# BPMicrocontroller.net
KiCad netlist of a schematic drawn in Altium Designer
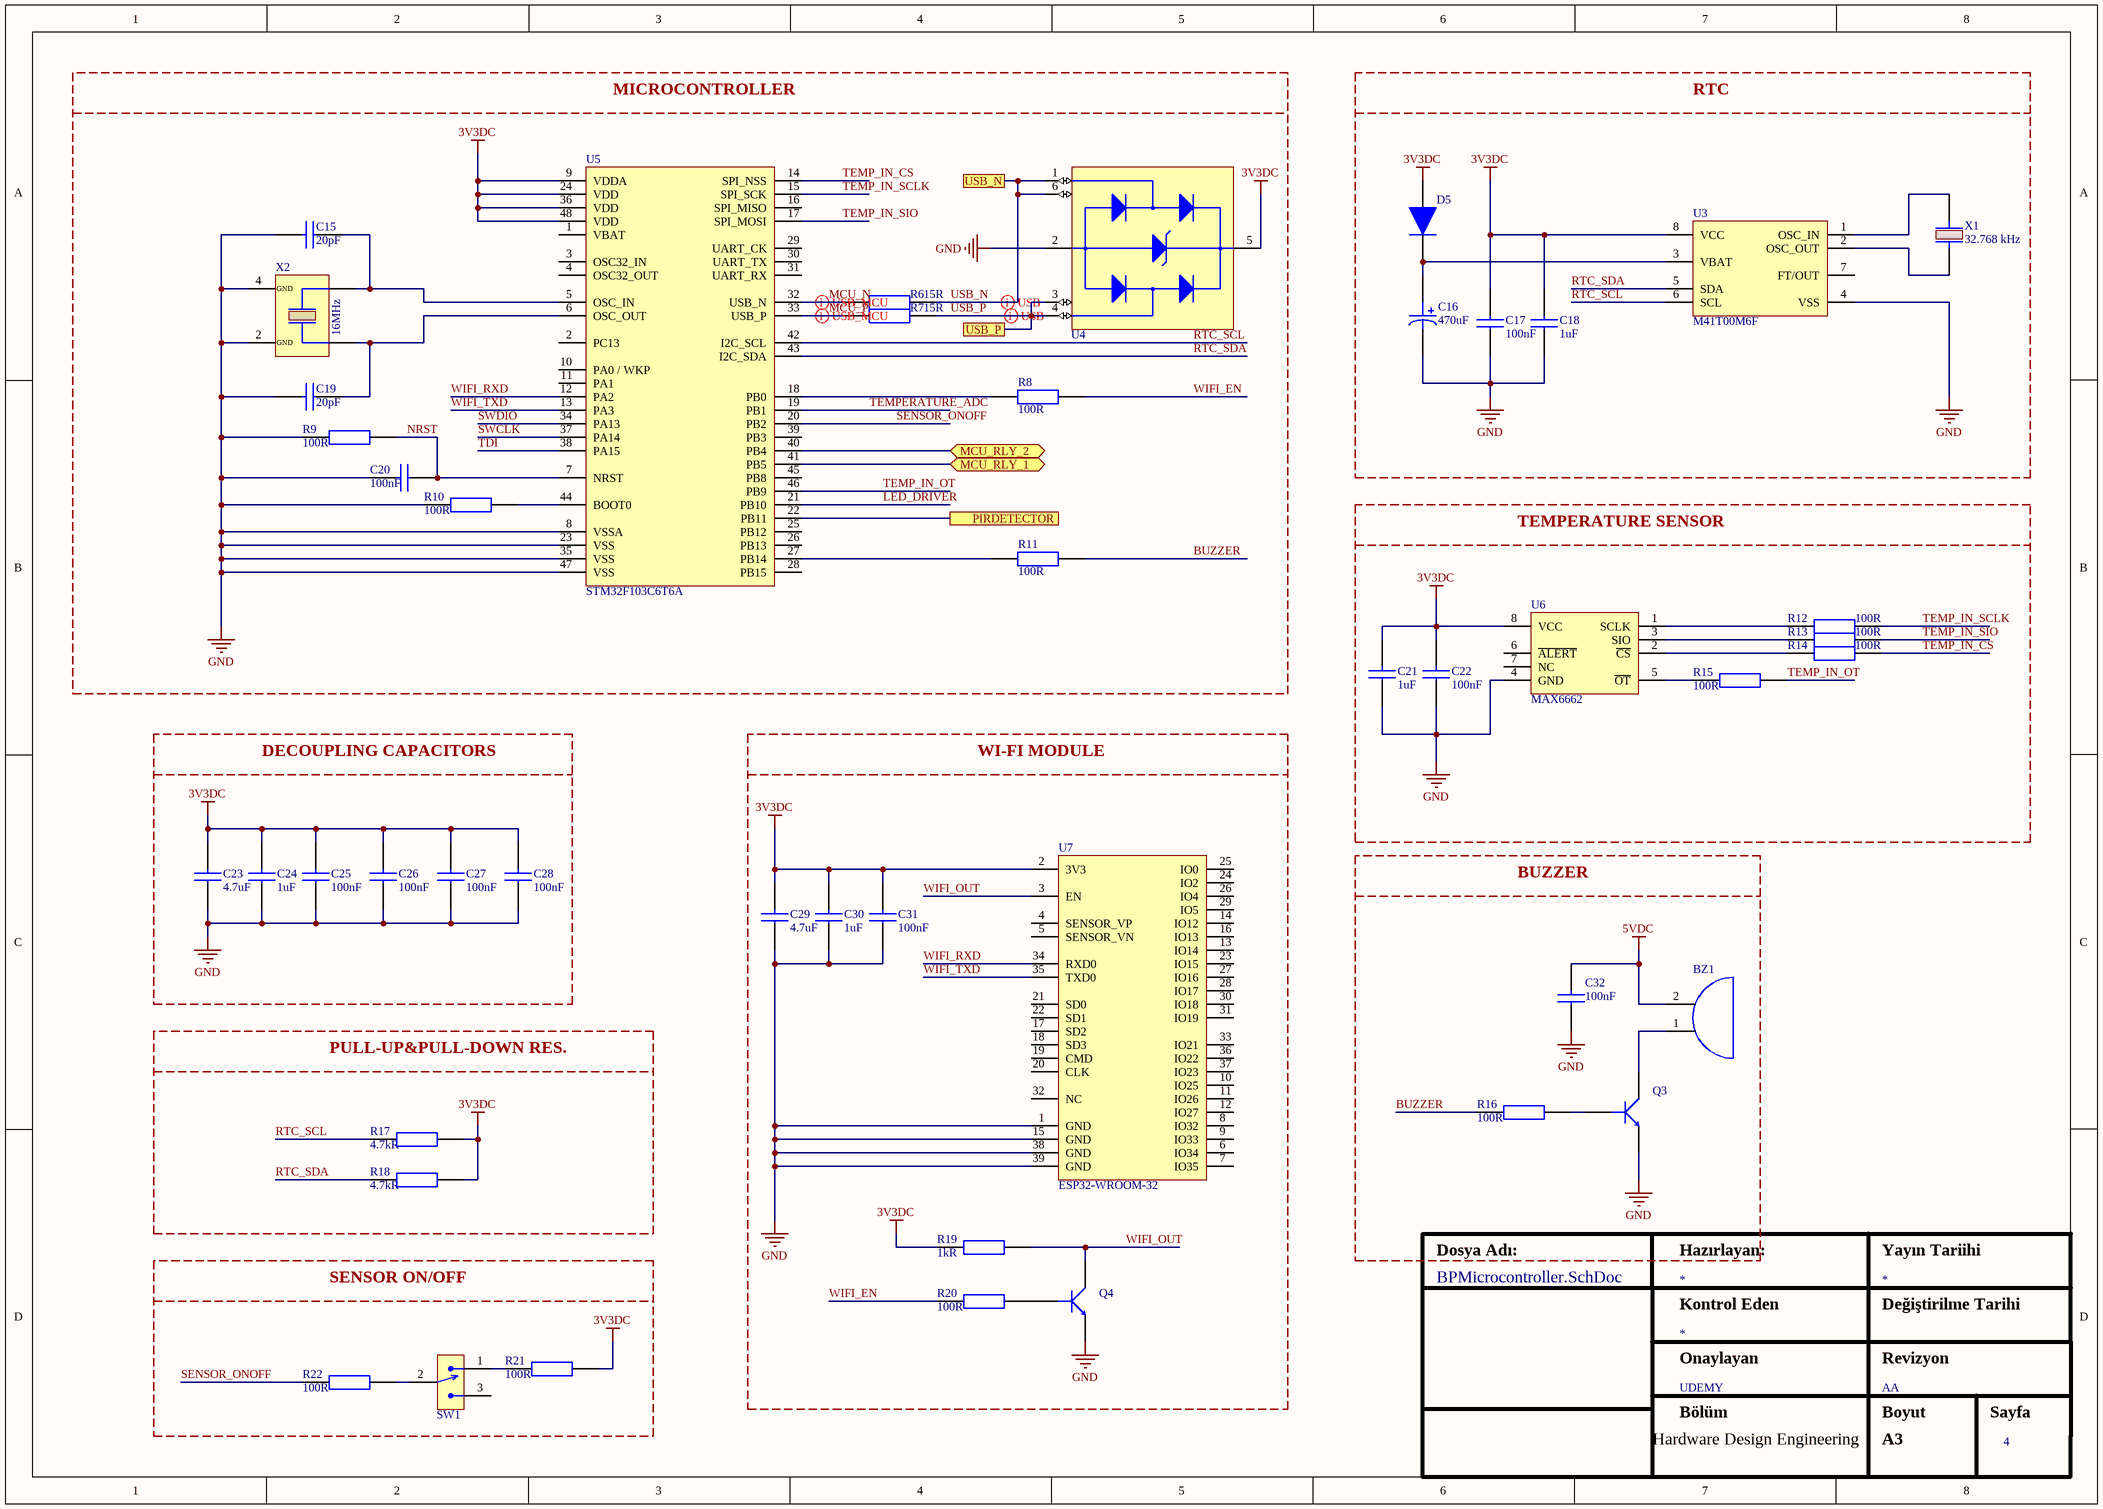
[diagram p0: BPMicrocontroller.SchDoc]

(export (version "E")
  (design (tool "Eeschema 10.0.6"))
  (components
    (comp (ref "BZ1")
      (value "CMI-9605IC-0580T")
      (footprint "CMI-9605IC")
      (description "Buzzers Indicator, Internally Driven Magnetic 5V 30mA 2.7kHz 80dB @ 5V, 10cm Through Hole PC Pins")
      (fields (field (name "MANUFACTURER") "CUI Devices") (field (name "DESIGNED BY") "BERK"))
      (libsource (lib "UDEMY_Library") (part "CMI-9605IC-0580T"))
    )
    (comp (ref "C15")
      (value "CL10C200JB8NNNC")
      (footprint "CAP_0603")
      (description "CAP CER 20pF %5 0603 SMD")
      (fields
        (field (name "MANUFACTURER") "Samsung")
        (field (name "TOLERANCE") "5%")
        (field (name "CAPACITANCE") "20pF")
        (field (name "DESIGNED BY") "BERK")
      )
      (libsource (lib "UDEMY_Library") (part "CAP CER 20pF 0603"))
    )
    (comp (ref "C16")
      (value "ESH477M050AH4AA")
      (footprint "CAP_RADIAL_D10_P5")
      (description "CAP ALU ELEC 470uF 50V RADIAL")
      (fields
        (field (name "MANUFACTURER") "KEMET")
        (field (name "TOLERANCE") "20%")
        (field (name "CAPACITANCE") "470uF")
        (field (name "DESIGNED BY") "BERK")
      )
      (libsource (lib "UDEMY_Library") (part "CAP ALU ELEC 470uF 50V"))
    )
    (comp (ref "C17")
      (value "CL21B104KBCNNNC")
      (footprint "CAP_0805")
      (description "CAP CER 100nF %10 0805")
      (fields
        (field (name "MANUFACTURER") "Samsung")
        (field (name "TOLERANCE") "10%")
        (field (name "CAPACITANCE") "100nF")
        (field (name "DESIGNED BY") "BERK")
      )
      (libsource (lib "UDEMY_Library") (part "CAP CER 100nF 0805"))
    )
    (comp (ref "C18")
      (value "CL21B105KBFNNNE")
      (footprint "CAP_0805")
      (description "CAP CER 1uF %10 0805")
      (fields
        (field (name "MANUFACTURER") "Samsung")
        (field (name "TOLERANCE") "10%")
        (field (name "CAPACITANCE") "1uF")
        (field (name "DESIGNED BY") "BERK")
      )
      (libsource (lib "UDEMY_Library") (part "CAP CER 1uF 0805"))
    )
    (comp (ref "C19")
      (value "CL10C200JB8NNNC")
      (footprint "CAP_0603")
      (description "CAP CER 20pF %5 0603 SMD")
      (fields
        (field (name "MANUFACTURER") "Samsung")
        (field (name "TOLERANCE") "5%")
        (field (name "CAPACITANCE") "20pF")
        (field (name "DESIGNED BY") "BERK")
      )
      (libsource (lib "UDEMY_Library") (part "CAP CER 20pF 0603"))
    )
    (comp (ref "C20")
      (value "C0603C104K5RACTU")
      (footprint "CAP_0603")
      (description "CAP CER 100nF %10 0603 SMD")
      (fields
        (field (name "MANUFACTURER") "KEMET")
        (field (name "TOLERANCE") "10%")
        (field (name "CAPACITANCE") "100nF")
        (field (name "DESIGNED BY") "BERK")
      )
      (libsource (lib "UDEMY_Library") (part "CAP CER 100nF 0603"))
    )
    (comp (ref "C21")
      (value "CL21B105KBFNNNE")
      (footprint "CAP_0805")
      (description "CAP CER 1uF %10 0805")
      (fields
        (field (name "MANUFACTURER") "Samsung")
        (field (name "TOLERANCE") "10%")
        (field (name "CAPACITANCE") "1uF")
        (field (name "DESIGNED BY") "BERK")
      )
      (libsource (lib "UDEMY_Library") (part "CAP CER 1uF 0805"))
    )
    (comp (ref "C22")
      (value "CL21B104KBCNNNC")
      (footprint "CAP_0805")
      (description "CAP CER 100nF %10 0805")
      (fields
        (field (name "MANUFACTURER") "Samsung")
        (field (name "TOLERANCE") "10%")
        (field (name "CAPACITANCE") "100nF")
        (field (name "DESIGNED BY") "BERK")
      )
      (libsource (lib "UDEMY_Library") (part "CAP CER 100nF 0805"))
    )
    (comp (ref "C23")
      (value "CL21A475KAQNNNE")
      (footprint "CAP_0805")
      (description "CAP CER 4.7uF %10 0805")
      (fields
        (field (name "MANUFACTURER") "Samsung")
        (field (name "TOLERANCE") "10%")
        (field (name "CAPACITANCE") "4.7uF")
        (field (name "DESIGNED BY") "BERK")
      )
      (libsource (lib "UDEMY_Library") (part "CAP CER 4.7uF 0805"))
    )
    (comp (ref "C24")
      (value "CL21B105KBFNNNE")
      (footprint "CAP_0805")
      (description "CAP CER 1uF %10 0805")
      (fields
        (field (name "MANUFACTURER") "Samsung")
        (field (name "TOLERANCE") "10%")
        (field (name "CAPACITANCE") "1uF")
        (field (name "DESIGNED BY") "BERK")
      )
      (libsource (lib "UDEMY_Library") (part "CAP CER 1uF 0805"))
    )
    (comp (ref "C25")
      (value "C0603C104K5RACTU")
      (footprint "CAP_0603")
      (description "CAP CER 100nF %10 0603 SMD")
      (fields
        (field (name "MANUFACTURER") "KEMET")
        (field (name "TOLERANCE") "10%")
        (field (name "CAPACITANCE") "100nF")
        (field (name "DESIGNED BY") "BERK")
      )
      (libsource (lib "UDEMY_Library") (part "CAP CER 100nF 0603"))
    )
    (comp (ref "C26")
      (value "C0603C104K5RACTU")
      (footprint "CAP_0603")
      (description "CAP CER 100nF %10 0603 SMD")
      (fields
        (field (name "MANUFACTURER") "KEMET")
        (field (name "TOLERANCE") "10%")
        (field (name "CAPACITANCE") "100nF")
        (field (name "DESIGNED BY") "BERK")
      )
      (libsource (lib "UDEMY_Library") (part "CAP CER 100nF 0603"))
    )
    (comp (ref "C27")
      (value "C0603C104K5RACTU")
      (footprint "CAP_0603")
      (description "CAP CER 100nF %10 0603 SMD")
      (fields
        (field (name "MANUFACTURER") "KEMET")
        (field (name "TOLERANCE") "10%")
        (field (name "CAPACITANCE") "100nF")
        (field (name "DESIGNED BY") "BERK")
      )
      (libsource (lib "UDEMY_Library") (part "CAP CER 100nF 0603"))
    )
    (comp (ref "C28")
      (value "C0603C104K5RACTU")
      (footprint "CAP_0603")
      (description "CAP CER 100nF %10 0603 SMD")
      (fields
        (field (name "MANUFACTURER") "KEMET")
        (field (name "TOLERANCE") "10%")
        (field (name "CAPACITANCE") "100nF")
        (field (name "DESIGNED BY") "BERK")
      )
      (libsource (lib "UDEMY_Library") (part "CAP CER 100nF 0603"))
    )
    (comp (ref "C29")
      (value "CL21A475KAQNNNE")
      (footprint "CAP_0805")
      (description "CAP CER 4.7uF %10 0805")
      (fields
        (field (name "MANUFACTURER") "Samsung")
        (field (name "TOLERANCE") "10%")
        (field (name "CAPACITANCE") "4.7uF")
        (field (name "DESIGNED BY") "BERK")
      )
      (libsource (lib "UDEMY_Library") (part "CAP CER 4.7uF 0805"))
    )
    (comp (ref "C30")
      (value "CL21B105KBFNNNE")
      (footprint "CAP_0805")
      (description "CAP CER 1uF %10 0805")
      (fields
        (field (name "MANUFACTURER") "Samsung")
        (field (name "TOLERANCE") "10%")
        (field (name "CAPACITANCE") "1uF")
        (field (name "DESIGNED BY") "BERK")
      )
      (libsource (lib "UDEMY_Library") (part "CAP CER 1uF 0805"))
    )
    (comp (ref "C31")
      (value "CL21B104KBCNNNC")
      (footprint "CAP_0805")
      (description "CAP CER 100nF %10 0805")
      (fields
        (field (name "MANUFACTURER") "Samsung")
        (field (name "TOLERANCE") "10%")
        (field (name "CAPACITANCE") "100nF")
        (field (name "DESIGNED BY") "BERK")
      )
      (libsource (lib "UDEMY_Library") (part "CAP CER 100nF 0805"))
    )
    (comp (ref "C32")
      (value "CL21B104KBCNNNC")
      (footprint "CAP_0805")
      (description "CAP CER 100nF %10 0805")
      (fields
        (field (name "MANUFACTURER") "Samsung")
        (field (name "TOLERANCE") "10%")
        (field (name "CAPACITANCE") "100nF")
        (field (name "DESIGNED BY") "BERK")
      )
      (libsource (lib "UDEMY_Library") (part "CAP CER 100nF 0805"))
    )
    (comp (ref "D5")
      (value "1N4148WS")
      (footprint "SOD323F")
      (description "Diode, Single, 75 V, 150 mA, 1 V, 4 ns")
      (fields
        (field (name "MANUFACTURER") "ON Semiconductor / Fairchild")
        (field (name "DESIGNED BY") "BERK")
      )
      (libsource (lib "UDEMY_Library") (part "1N4148WS"))
    )
    (comp (ref "Q3")
      (value "MMBT3904-7-F")
      (footprint "SOT-23F")
      (description "Transistor General Purpose BJT NPN 40 Volt 0.2A Automotive 3-Pin SOT-23")
      (fields (field (name "MANUFACTURER") "Diodes Zetex") (field (name "DESIGNED BY") "BERK"))
      (libsource (lib "UDEMY_Library") (part "MMBT3904-7-F"))
    )
    (comp (ref "Q4")
      (value "MMBT3904-7-F")
      (footprint "SOT-23F")
      (description "Transistor General Purpose BJT NPN 40 Volt 0.2A Automotive 3-Pin SOT-23")
      (fields (field (name "MANUFACTURER") "Diodes Zetex") (field (name "DESIGNED BY") "BERK"))
      (libsource (lib "UDEMY_Library") (part "MMBT3904-7-F"))
    )
    (comp (ref "R6")
      (value "RC0603JR-0715RL")
      (footprint "RES_0603")
      (description "RES 15 %5 OHM 0603 SMD")
      (fields
        (field (name "MANUFACTURER") "Yageo")
        (field (name "TOLERANCE") "5%")
        (field (name "RESISTANCE") "15R")
        (field (name "DESIGNED BY") "BERK")
      )
      (libsource (lib "UDEMY_Library") (part "RES 15 OHM 0603"))
    )
    (comp (ref "R7")
      (value "RC0603JR-0715RL")
      (footprint "RES_0603")
      (description "RES 15 %5 OHM 0603 SMD")
      (fields
        (field (name "MANUFACTURER") "Yageo")
        (field (name "TOLERANCE") "5%")
        (field (name "RESISTANCE") "15R")
        (field (name "DESIGNED BY") "BERK")
      )
      (libsource (lib "UDEMY_Library") (part "RES 15 OHM 0603"))
    )
    (comp (ref "R8")
      (value "RC0603JR-07100RL")
      (footprint "RES_0603")
      (description "RES 100 %5 OHM 0603 SMD")
      (fields
        (field (name "MANUFACTURER") "Yageo")
        (field (name "TOLERANCE") "5%")
        (field (name "RESISTANCE") "100R")
        (field (name "DESIGNED BY") "BERK")
      )
      (libsource (lib "UDEMY_Library") (part "RES 100 OHM 0603"))
    )
    (comp (ref "R9")
      (value "RC0603JR-07100RL")
      (footprint "RES_0603")
      (description "RES 100 %5 OHM 0603 SMD")
      (fields
        (field (name "MANUFACTURER") "Yageo")
        (field (name "TOLERANCE") "5%")
        (field (name "RESISTANCE") "100R")
        (field (name "DESIGNED BY") "BERK")
      )
      (libsource (lib "UDEMY_Library") (part "RES 100 OHM 0603"))
    )
    (comp (ref "R10")
      (value "RC0603JR-07100RL")
      (footprint "RES_0603")
      (description "RES 100 %5 OHM 0603 SMD")
      (fields
        (field (name "MANUFACTURER") "Yageo")
        (field (name "TOLERANCE") "5%")
        (field (name "RESISTANCE") "100R")
        (field (name "DESIGNED BY") "BERK")
      )
      (libsource (lib "UDEMY_Library") (part "RES 100 OHM 0603"))
    )
    (comp (ref "R11")
      (value "RC0603JR-07100RL")
      (footprint "RES_0603")
      (description "RES 100 %5 OHM 0603 SMD")
      (fields
        (field (name "MANUFACTURER") "Yageo")
        (field (name "TOLERANCE") "5%")
        (field (name "RESISTANCE") "100R")
        (field (name "DESIGNED BY") "BERK")
      )
      (libsource (lib "UDEMY_Library") (part "RES 100 OHM 0603"))
    )
    (comp (ref "R12")
      (value "RC0603JR-07100RL")
      (footprint "RES_0603")
      (description "RES 100 %5 OHM 0603 SMD")
      (fields
        (field (name "MANUFACTURER") "Yageo")
        (field (name "TOLERANCE") "5%")
        (field (name "RESISTANCE") "100R")
        (field (name "DESIGNED BY") "BERK")
      )
      (libsource (lib "UDEMY_Library") (part "RES 100 OHM 0603"))
    )
    (comp (ref "R13")
      (value "RC0603JR-07100RL")
      (footprint "RES_0603")
      (description "RES 100 %5 OHM 0603 SMD")
      (fields
        (field (name "MANUFACTURER") "Yageo")
        (field (name "TOLERANCE") "5%")
        (field (name "RESISTANCE") "100R")
        (field (name "DESIGNED BY") "BERK")
      )
      (libsource (lib "UDEMY_Library") (part "RES 100 OHM 0603"))
    )
    (comp (ref "R14")
      (value "RC0603JR-07100RL")
      (footprint "RES_0603")
      (description "RES 100 %5 OHM 0603 SMD")
      (fields
        (field (name "MANUFACTURER") "Yageo")
        (field (name "TOLERANCE") "5%")
        (field (name "RESISTANCE") "100R")
        (field (name "DESIGNED BY") "BERK")
      )
      (libsource (lib "UDEMY_Library") (part "RES 100 OHM 0603"))
    )
    (comp (ref "R15")
      (value "RC0603JR-07100RL")
      (footprint "RES_0603")
      (description "RES 100 %5 OHM 0603 SMD")
      (fields
        (field (name "MANUFACTURER") "Yageo")
        (field (name "TOLERANCE") "5%")
        (field (name "RESISTANCE") "100R")
        (field (name "DESIGNED BY") "BERK")
      )
      (libsource (lib "UDEMY_Library") (part "RES 100 OHM 0603"))
    )
    (comp (ref "R16")
      (value "RC0603JR-07100RL")
      (footprint "RES_0603")
      (description "RES 100 %5 OHM 0603 SMD")
      (fields
        (field (name "MANUFACTURER") "Yageo")
        (field (name "TOLERANCE") "5%")
        (field (name "RESISTANCE") "100R")
        (field (name "DESIGNED BY") "BERK")
      )
      (libsource (lib "UDEMY_Library") (part "RES 100 OHM 0603"))
    )
    (comp (ref "R17")
      (value "RC0603JR-074K7L")
      (footprint "RES_0603")
      (description "RES 4K7 %5 OHM 0603 SMD")
      (fields
        (field (name "MANUFACTURER") "Yageo")
        (field (name "TOLERANCE") "5%")
        (field (name "RESISTANCE") "4.7kR")
        (field (name "DESIGNED BY") "BERK")
      )
      (libsource (lib "UDEMY_Library") (part "RES 4K7 OHM 0603"))
    )
    (comp (ref "R18")
      (value "RC0603JR-074K7L")
      (footprint "RES_0603")
      (description "RES 4K7 %5 OHM 0603 SMD")
      (fields
        (field (name "MANUFACTURER") "Yageo")
        (field (name "TOLERANCE") "5%")
        (field (name "RESISTANCE") "4.7kR")
        (field (name "DESIGNED BY") "BERK")
      )
      (libsource (lib "UDEMY_Library") (part "RES 4K7 OHM 0603"))
    )
    (comp (ref "R19")
      (value "RC0603FR-0710KL")
      (footprint "RES_0603")
      (description "RES 1K %1 OHM 0603 SMD")
      (fields
        (field (name "MANUFACTURER") "Yageo")
        (field (name "MANUFACTURER PART NUMBER") "RC0603JR-071KL")
        (field (name "RESISTANCE") "1kR")
        (field (name "DESIGNED BY") "BERK")
      )
      (libsource (lib "UDEMY_Library") (part "RES 1K OHM 0603"))
    )
    (comp (ref "R20")
      (value "RC0603JR-07100RL")
      (footprint "RES_0603")
      (description "RES 100 %5 OHM 0603 SMD")
      (fields
        (field (name "MANUFACTURER") "Yageo")
        (field (name "TOLERANCE") "5%")
        (field (name "RESISTANCE") "100R")
        (field (name "DESIGNED BY") "BERK")
      )
      (libsource (lib "UDEMY_Library") (part "RES 100 OHM 0603"))
    )
    (comp (ref "R21")
      (value "RC0603JR-07100RL")
      (footprint "RES_0603")
      (description "RES 100 %5 OHM 0603 SMD")
      (fields
        (field (name "MANUFACTURER") "Yageo")
        (field (name "TOLERANCE") "5%")
        (field (name "RESISTANCE") "100R")
        (field (name "DESIGNED BY") "BERK")
      )
      (libsource (lib "UDEMY_Library") (part "RES 100 OHM 0603"))
    )
    (comp (ref "R22")
      (value "RC0603JR-07100RL")
      (footprint "RES_0603")
      (description "RES 100 %5 OHM 0603 SMD")
      (fields
        (field (name "MANUFACTURER") "Yageo")
        (field (name "TOLERANCE") "5%")
        (field (name "RESISTANCE") "100R")
        (field (name "DESIGNED BY") "BERK")
      )
      (libsource (lib "") (part "RES 100 OHM 0603_1"))
    )
    (comp (ref "SW1")
      (value "EG1215AA")
      (footprint "EG1215AA")
      (description "Slide Switch, SPDT, 0.025A, 24V, SMD")
      (fields
        (field (name "MANUFACTURER") "E-Switch")
        (field (name "TOLERANCE") "4.95%")
        (field (name "DESIGNED BY") "BERK")
      )
      (libsource (lib "UDEMY_Library") (part "EG1215AA"))
    )
    (comp (ref "U3")
      (value "M41T00M6F")
      (footprint "SOIC8")
      (description "IC RTC CLK/CALENDAR I2C 8-SOIC")
      (fields (field (name "MANUFACTURER") "STMicroelectronics") (field (name "DESIGNED BY") "BERK"))
      (libsource (lib "UDEMY_Library") (part "M41T00M6F"))
    )
    (comp (ref "U4")
      (value "USBLC6-2SC6")
      (footprint "SOT23-6L")
      (description "TVS DIODE 5.25V 17V SOT23-6")
      (fields (field (name "MANUFACTURER") "STMicroelectronics") (field (name "DESIGNED BY") "BERK"))
      (libsource (lib "UDEMY_Library") (part "USB PROTECTION"))
    )
    (comp (ref "U5")
      (value "STM32F103C6T6A")
      (footprint "LQFP-48")
      (description "MCU 32-bit STM32F ARM Cortex M3 RISC 32KB Flash 2.5V/3.3V 48-Pin LQFP Tray")
      (fields (field (name "MANUFACTURER") "STMicroelectronics") (field (name "DESIGNED BY") "BERK"))
      (libsource (lib "UDEMY_Library") (part "STM32F103C6T6A"))
    )
    (comp (ref "U6")
      (value "MAX6662")
      (footprint "SOIC8")
      (description "SENSOR TEMPERATURE SPI 8SOIC")
      (fields
        (field (name "MANUFACTURER") "Maxim")
        (field (name "MANUFACTURER PART NUMBER") "MAX6662MSA+")
        (field (name "DESIGNED BY") "BERK")
      )
      (libsource (lib "UDEMY_Library") (part "MAX6662"))
    )
    (comp (ref "U7")
      (value "ESP32-WROOM-32")
      (footprint "ESP32-32")
      (description "SMD MODULE, ESP32-D0WDQ6, 32MBIT")
      (fields (field (name "MANUFACTURER") "Espressif Systems") (field (name "DESIGNED BY") "BERK"))
      (libsource (lib "UDEMY_Library") (part "ESP32-WROOM-32"))
    )
    (comp (ref "X1")
      (value "ABS05-32.768KHZ-T")
      (footprint "BPSchematic:ABS05")
      (description "Crystal, 32.768 kHz, SMD, 1.6mm x 1mm, 12.5 pF, 20 ppm, ABS05 Series")
      (fields
        (field (name "MANUFACTURER") "Abracon")
        (field (name "TOLERANCE") "20ppm")
        (field (name "OPERATING FREQUENCY") "32.768 kHz")
        (field (name "DESIGNED BY") "BERK")
      )
      (libsource (lib "UDEMY_Library") (part "CRYSTAL 32768kHZ"))
    )
    (comp (ref "X2")
      (value "ECS-160-20-30B-TR")
      (footprint "ECS")
      (description "CRYSTAL 16.0000MHZ 20PF SMD")
      (fields
        (field (name "MANUFACTURER") "ECS International")
        (field (name "TOLERANCE") "50ppm")
        (field (name "FREQUENCY") "16MHz")
        (field (name "DESIGNED BY") "BERK")
      )
      (libsource (lib "UDEMY_Library") (part "CRYSTAL 16MHz"))
    )
  )
  (nets
    (net (code "1") (name "/BUZZER") (class "Default")
      (node (ref "R11") (pin "2") (pinfunction "2_2") (pintype "passive"))
      (node (ref "R16") (pin "1") (pinfunction "1_1") (pintype "passive"))
    )
    (net (code "2") (name "/LED_DRIVER") (class "Default")
      (node (ref "U5") (pin "21") (pinfunction "PB10_21") (pintype "passive"))
    )
    (net (code "3") (name "/MCU_N") (class "Default")
      (node (ref "R6") (pin "1") (pinfunction "1_1") (pintype "passive"))
      (node (ref "U5") (pin "32") (pinfunction "USB_N_32") (pintype "passive"))
    )
    (net (code "4") (name "/MCU_P") (class "Default")
      (node (ref "R7") (pin "1") (pinfunction "1_1") (pintype "passive"))
      (node (ref "U5") (pin "33") (pinfunction "USB_P_33") (pintype "passive"))
    )
    (net (code "5") (name "/MCU_RLY_1") (class "Default")
      (node (ref "U5") (pin "41") (pinfunction "PB5_41") (pintype "passive"))
    )
    (net (code "6") (name "/MCU_RLY_2") (class "Default")
      (node (ref "U5") (pin "40") (pinfunction "PB4_40") (pintype "passive"))
    )
    (net (code "7") (name "/NRST") (class "Default")
      (node (ref "C20") (pin "1") (pinfunction "1_1") (pintype "passive"))
      (node (ref "R9") (pin "2") (pinfunction "2_2") (pintype "passive"))
      (node (ref "U5") (pin "7") (pinfunction "NRST_7") (pintype "passive"))
    )
    (net (code "8") (name "/PIRDETECTOR") (class "Default")
      (node (ref "U5") (pin "22") (pinfunction "PB11_22") (pintype "passive"))
    )
    (net (code "9") (name "/RTC_SCL") (class "Default")
      (node (ref "R17") (pin "1") (pinfunction "1_1") (pintype "passive"))
      (node (ref "U3") (pin "6") (pinfunction "SCL_6") (pintype "passive"))
      (node (ref "U5") (pin "42") (pinfunction "I2C_SCL_42") (pintype "passive"))
    )
    (net (code "10") (name "/RTC_SDA") (class "Default")
      (node (ref "R18") (pin "1") (pinfunction "1_1") (pintype "passive"))
      (node (ref "U3") (pin "5") (pinfunction "SDA_5") (pintype "passive"))
      (node (ref "U5") (pin "43") (pinfunction "I2C_SDA_43") (pintype "passive"))
    )
    (net (code "11") (name "/SENSOR_ONOFF") (class "Default")
      (node (ref "R22") (pin "2") (pinfunction "2_2") (pintype "passive"))
      (node (ref "U5") (pin "20") (pinfunction "PB2_20") (pintype "passive"))
    )
    (net (code "12") (name "/SWCLK") (class "Default")
      (node (ref "U5") (pin "37") (pinfunction "PA14_37") (pintype "passive"))
    )
    (net (code "13") (name "/SWDIO") (class "Default")
      (node (ref "U5") (pin "34") (pinfunction "PA13_34") (pintype "passive"))
    )
    (net (code "14") (name "/TDI") (class "Default")
      (node (ref "U5") (pin "38") (pinfunction "PA15_38") (pintype "passive"))
    )
    (net (code "15") (name "/TEMPERATURE_ADC") (class "Default")
      (node (ref "U5") (pin "19") (pinfunction "PB1_19") (pintype "passive"))
    )
    (net (code "16") (name "/TEMP_IN_CS") (class "Default")
      (node (ref "R14") (pin "2") (pinfunction "2_2") (pintype "passive"))
      (node (ref "U5") (pin "14") (pinfunction "SPI_NSS_14") (pintype "passive"))
    )
    (net (code "17") (name "/TEMP_IN_OT") (class "Default")
      (node (ref "R15") (pin "2") (pinfunction "2_2") (pintype "passive"))
      (node (ref "U5") (pin "46") (pinfunction "PB9_46") (pintype "passive"))
    )
    (net (code "18") (name "/TEMP_IN_SCLK") (class "Default")
      (node (ref "R12") (pin "2") (pinfunction "2_2") (pintype "passive"))
      (node (ref "U5") (pin "15") (pinfunction "SPI_SCK_15") (pintype "passive"))
    )
    (net (code "19") (name "/TEMP_IN_SIO") (class "Default")
      (node (ref "R13") (pin "2") (pinfunction "2_2") (pintype "passive"))
      (node (ref "U5") (pin "17") (pinfunction "SPI_MOSI_17") (pintype "passive"))
    )
    (net (code "20") (name "/USB_N") (class "Default")
      (node (ref "R6") (pin "2") (pinfunction "2_2") (pintype "passive"))
      (node (ref "U4") (pin "1") (pinfunction "I/O1_1") (pintype "bidirectional"))
      (node (ref "U4") (pin "6") (pinfunction "I/O1_6") (pintype "bidirectional"))
    )
    (net (code "21") (name "/USB_P") (class "Default")
      (node (ref "R7") (pin "2") (pinfunction "2_2") (pintype "passive"))
      (node (ref "U4") (pin "3") (pinfunction "I/O2_3") (pintype "bidirectional"))
      (node (ref "U4") (pin "4") (pinfunction "I/O2_4") (pintype "bidirectional"))
    )
    (net (code "22") (name "/WIFI_EN") (class "Default")
      (node (ref "R20") (pin "1") (pinfunction "1_1") (pintype "passive"))
      (node (ref "R8") (pin "2") (pinfunction "2_2") (pintype "passive"))
    )
    (net (code "23") (name "/WIFI_OUT") (class "Default")
      (node (ref "Q4") (pin "3") (pinfunction "C_3") (pintype "power_in"))
      (node (ref "R19") (pin "1") (pinfunction "1_1") (pintype "passive"))
      (node (ref "U7") (pin "3") (pinfunction "EN_3") (pintype "passive"))
    )
    (net (code "24") (name "/WIFI_RXD") (class "Default")
      (node (ref "U5") (pin "12") (pinfunction "PA2_12") (pintype "passive"))
      (node (ref "U7") (pin "34") (pinfunction "RXD0_34") (pintype "passive"))
    )
    (net (code "25") (name "/WIFI_TXD") (class "Default")
      (node (ref "U5") (pin "13") (pinfunction "PA3_13") (pintype "passive"))
      (node (ref "U7") (pin "35") (pinfunction "TXD0_35") (pintype "passive"))
    )
    (net (code "26") (name "3V3DC") (class "Default")
      (node (ref "C17") (pin "2") (pinfunction "2_2") (pintype "passive"))
      (node (ref "C18") (pin "2") (pinfunction "2_2") (pintype "passive"))
      (node (ref "C21") (pin "2") (pinfunction "2_2") (pintype "passive"))
      (node (ref "C22") (pin "2") (pinfunction "2_2") (pintype "passive"))
      (node (ref "C23") (pin "2") (pinfunction "2_2") (pintype "passive"))
      (node (ref "C24") (pin "2") (pinfunction "2_2") (pintype "passive"))
      (node (ref "C25") (pin "2") (pinfunction "2_2") (pintype "passive"))
      (node (ref "C26") (pin "2") (pinfunction "2_2") (pintype "passive"))
      (node (ref "C27") (pin "2") (pinfunction "2_2") (pintype "passive"))
      (node (ref "C28") (pin "2") (pinfunction "2_2") (pintype "passive"))
      (node (ref "C29") (pin "2") (pinfunction "2_2") (pintype "passive"))
      (node (ref "C30") (pin "2") (pinfunction "2_2") (pintype "passive"))
      (node (ref "C31") (pin "2") (pinfunction "2_2") (pintype "passive"))
      (node (ref "D5") (pin "2") (pinfunction "2_2") (pintype "power_in"))
      (node (ref "R17") (pin "2") (pinfunction "2_2") (pintype "passive"))
      (node (ref "R18") (pin "2") (pinfunction "2_2") (pintype "passive"))
      (node (ref "R19") (pin "2") (pinfunction "2_2") (pintype "passive"))
      (node (ref "R21") (pin "2") (pinfunction "2_2") (pintype "passive"))
      (node (ref "U3") (pin "8") (pinfunction "VCC_8") (pintype "passive"))
      (node (ref "U4") (pin "5") (pinfunction "VBUS_5") (pintype "power_in"))
      (node (ref "U5") (pin "24") (pinfunction "VDD_24") (pintype "passive"))
      (node (ref "U5") (pin "36") (pinfunction "VDD_36") (pintype "passive"))
      (node (ref "U5") (pin "48") (pinfunction "VDD_48") (pintype "passive"))
      (node (ref "U5") (pin "9") (pinfunction "VDDA_9") (pintype "passive"))
      (node (ref "U6") (pin "8") (pinfunction "VCC_8") (pintype "passive"))
      (node (ref "U7") (pin "2") (pinfunction "3V3_2") (pintype "passive"))
    )
    (net (code "27") (name "5VDC") (class "Default")
      (node (ref "BZ1") (pin "2") (pinfunction "2_2") (pintype "passive"))
      (node (ref "C32") (pin "2") (pinfunction "2_2") (pintype "passive"))
    )
    (net (code "28") (name "GND") (class "Default")
      (node (ref "C15") (pin "2") (pinfunction "2_2") (pintype "passive"))
      (node (ref "C16") (pin "2") (pinfunction "2_2") (pintype "passive"))
      (node (ref "C17") (pin "1") (pinfunction "1_1") (pintype "passive"))
      (node (ref "C18") (pin "1") (pinfunction "1_1") (pintype "passive"))
      (node (ref "C19") (pin "2") (pinfunction "2_2") (pintype "passive"))
      (node (ref "C20") (pin "2") (pinfunction "2_2") (pintype "passive"))
      (node (ref "C21") (pin "1") (pinfunction "1_1") (pintype "passive"))
      (node (ref "C22") (pin "1") (pinfunction "1_1") (pintype "passive"))
      (node (ref "C23") (pin "1") (pinfunction "1_1") (pintype "passive"))
      (node (ref "C24") (pin "1") (pinfunction "1_1") (pintype "passive"))
      (node (ref "C25") (pin "1") (pinfunction "1_1") (pintype "passive"))
      (node (ref "C26") (pin "1") (pinfunction "1_1") (pintype "passive"))
      (node (ref "C27") (pin "1") (pinfunction "1_1") (pintype "passive"))
      (node (ref "C28") (pin "1") (pinfunction "1_1") (pintype "passive"))
      (node (ref "C29") (pin "1") (pinfunction "1_1") (pintype "passive"))
      (node (ref "C30") (pin "1") (pinfunction "1_1") (pintype "passive"))
      (node (ref "C31") (pin "1") (pinfunction "1_1") (pintype "passive"))
      (node (ref "C32") (pin "1") (pinfunction "1_1") (pintype "passive"))
      (node (ref "Q3") (pin "2") (pinfunction "E_2") (pintype "power_in"))
      (node (ref "Q4") (pin "2") (pinfunction "E_2") (pintype "power_in"))
      (node (ref "R10") (pin "1") (pinfunction "1_1") (pintype "passive"))
      (node (ref "R9") (pin "1") (pinfunction "1_1") (pintype "passive"))
      (node (ref "U3") (pin "4") (pinfunction "VSS_4") (pintype "passive"))
      (node (ref "U4") (pin "2") (pinfunction "GND_2") (pintype "power_in"))
      (node (ref "U5") (pin "23") (pinfunction "VSS_23") (pintype "passive"))
      (node (ref "U5") (pin "35") (pinfunction "VSS_35") (pintype "passive"))
      (node (ref "U5") (pin "47") (pinfunction "VSS_47") (pintype "passive"))
      (node (ref "U5") (pin "8") (pinfunction "VSSA_8") (pintype "passive"))
      (node (ref "U6") (pin "4") (pinfunction "GND_4") (pintype "passive"))
      (node (ref "U7") (pin "1") (pinfunction "GND_1") (pintype "passive"))
      (node (ref "U7") (pin "15") (pinfunction "GND_15") (pintype "passive"))
      (node (ref "U7") (pin "38") (pinfunction "GND_38") (pintype "passive"))
      (node (ref "U7") (pin "39") (pinfunction "GND_39") (pintype "passive"))
      (node (ref "X2") (pin "2") (pinfunction "GND_2") (pintype "passive"))
      (node (ref "X2") (pin "4") (pinfunction "GND_4") (pintype "passive"))
    )
    (net (code "29") (name "Net-(Q3-B)") (class "Default")
      (node (ref "Q3") (pin "1") (pinfunction "B_1") (pintype "power_in"))
      (node (ref "R16") (pin "2") (pinfunction "2_2") (pintype "passive"))
    )
    (net (code "30") (name "Net-(Q3-C)") (class "Default")
      (node (ref "BZ1") (pin "1") (pinfunction "1_1") (pintype "passive"))
      (node (ref "Q3") (pin "3") (pinfunction "C_3") (pintype "power_in"))
    )
    (net (code "31") (name "Net-(Q4-B)") (class "Default")
      (node (ref "Q4") (pin "1") (pinfunction "B_1") (pintype "power_in"))
      (node (ref "R20") (pin "2") (pinfunction "2_2") (pintype "passive"))
    )
    (net (code "32") (name "Net-(R21-Pad1)") (class "Default")
      (node (ref "R21") (pin "1") (pinfunction "1_1") (pintype "passive"))
      (node (ref "SW1") (pin "1") (pinfunction "1_1") (pintype "passive"))
    )
    (net (code "33") (name "Net-(R22-Pad1)") (class "Default")
      (node (ref "R22") (pin "1") (pinfunction "1_1") (pintype "passive"))
      (node (ref "SW1") (pin "2") (pinfunction "2_2") (pintype "passive"))
    )
    (net (code "34") (name "Net-(U3-OSC_IN)") (class "Default")
      (node (ref "U3") (pin "1") (pinfunction "OSC_IN_1") (pintype "passive"))
      (node (ref "X1") (pin "2") (pinfunction "2_2") (pintype "passive"))
    )
    (net (code "35") (name "Net-(U3-OSC_OUT)") (class "Default")
      (node (ref "U3") (pin "2") (pinfunction "OSC_OUT_2") (pintype "passive"))
      (node (ref "X1") (pin "1") (pinfunction "1_1") (pintype "passive"))
    )
    (net (code "36") (name "Net-(U3-VBAT)") (class "Default")
      (node (ref "C16") (pin "1") (pinfunction "1_1") (pintype "passive"))
      (node (ref "D5") (pin "1") (pinfunction "1_1") (pintype "power_in"))
      (node (ref "U3") (pin "3") (pinfunction "VBAT_3") (pintype "passive"))
    )
    (net (code "37") (name "Net-(U5-BOOT0)") (class "Default")
      (node (ref "R10") (pin "2") (pinfunction "2_2") (pintype "passive"))
      (node (ref "U5") (pin "44") (pinfunction "BOOT0_44") (pintype "passive"))
    )
    (net (code "38") (name "Net-(U5-OSC_IN)") (class "Default")
      (node (ref "C15") (pin "1") (pinfunction "1_1") (pintype "passive"))
      (node (ref "U5") (pin "5") (pinfunction "OSC_IN_5") (pintype "passive"))
      (node (ref "X2") (pin "3") (pinfunction "3_3") (pintype "passive"))
    )
    (net (code "39") (name "Net-(U5-OSC_OUT)") (class "Default")
      (node (ref "C19") (pin "1") (pinfunction "1_1") (pintype "passive"))
      (node (ref "U5") (pin "6") (pinfunction "OSC_OUT_6") (pintype "passive"))
      (node (ref "X2") (pin "1") (pinfunction "1_1") (pintype "passive"))
    )
    (net (code "40") (name "Net-(U5-PB0)") (class "Default")
      (node (ref "R8") (pin "1") (pinfunction "1_1") (pintype "passive"))
      (node (ref "U5") (pin "18") (pinfunction "PB0_18") (pintype "passive"))
    )
    (net (code "41") (name "Net-(U5-PB14)") (class "Default")
      (node (ref "R11") (pin "1") (pinfunction "1_1") (pintype "passive"))
      (node (ref "U5") (pin "27") (pinfunction "PB14_27") (pintype "passive"))
    )
    (net (code "42") (name "Net-(U6-SCLK)") (class "Default")
      (node (ref "R12") (pin "1") (pinfunction "1_1") (pintype "passive"))
      (node (ref "U6") (pin "1") (pinfunction "SCLK_1") (pintype "passive"))
    )
    (net (code "43") (name "Net-(U6-SIO)") (class "Default")
      (node (ref "R13") (pin "1") (pinfunction "1_1") (pintype "passive"))
      (node (ref "U6") (pin "3") (pinfunction "SIO_3") (pintype "passive"))
    )
    (net (code "44") (name "Net-(U6-~{CS})") (class "Default")
      (node (ref "R14") (pin "1") (pinfunction "1_1") (pintype "passive"))
      (node (ref "U6") (pin "2") (pinfunction "~{CS}_2") (pintype "passive"))
    )
    (net (code "45") (name "Net-(U6-~{OT})") (class "Default")
      (node (ref "R15") (pin "1") (pinfunction "1_1") (pintype "passive"))
      (node (ref "U6") (pin "5") (pinfunction "~{OT}_5") (pintype "passive"))
    )
    (net (code "46") (name "unconnected-(SW1-Pad3)") (class "Default")
      (node (ref "SW1") (pin "3") (pinfunction "3_3") (pintype "passive"))
    )
    (net (code "47") (name "unconnected-(U3-FT{slash}OUT-Pad7)") (class "Default")
      (node (ref "U3") (pin "7") (pinfunction "FT/OUT_7") (pintype "passive"))
    )
    (net (code "48") (name "unconnected-(U5-OSC32_IN-Pad3)") (class "Default")
      (node (ref "U5") (pin "3") (pinfunction "OSC32_IN_3") (pintype "passive"))
    )
    (net (code "49") (name "unconnected-(U5-OSC32_OUT-Pad4)") (class "Default")
      (node (ref "U5") (pin "4") (pinfunction "OSC32_OUT_4") (pintype "passive"))
    )
    (net (code "50") (name "unconnected-(U5-PA0_{slash}_WKP-Pad10)") (class "Default")
      (node (ref "U5") (pin "10") (pinfunction "PA0_/_WKP_10") (pintype "passive"))
    )
    (net (code "51") (name "unconnected-(U5-PA1-Pad11)") (class "Default")
      (node (ref "U5") (pin "11") (pinfunction "PA1_11") (pintype "passive"))
    )
    (net (code "52") (name "unconnected-(U5-PB3-Pad39)") (class "Default")
      (node (ref "U5") (pin "39") (pinfunction "PB3_39") (pintype "passive"))
    )
    (net (code "53") (name "unconnected-(U5-PB8-Pad45)") (class "Default")
      (node (ref "U5") (pin "45") (pinfunction "PB8_45") (pintype "passive"))
    )
    (net (code "54") (name "unconnected-(U5-PB12-Pad25)") (class "Default")
      (node (ref "U5") (pin "25") (pinfunction "PB12_25") (pintype "passive"))
    )
    (net (code "55") (name "unconnected-(U5-PB13-Pad26)") (class "Default")
      (node (ref "U5") (pin "26") (pinfunction "PB13_26") (pintype "passive"))
    )
    (net (code "56") (name "unconnected-(U5-PB15-Pad28)") (class "Default")
      (node (ref "U5") (pin "28") (pinfunction "PB15_28") (pintype "passive"))
    )
    (net (code "57") (name "unconnected-(U5-PC13-Pad2)") (class "Default")
      (node (ref "U5") (pin "2") (pinfunction "PC13_2") (pintype "passive"))
    )
    (net (code "58") (name "unconnected-(U5-SPI_MISO-Pad16)") (class "Default")
      (node (ref "U5") (pin "16") (pinfunction "SPI_MISO_16") (pintype "passive"))
    )
    (net (code "59") (name "unconnected-(U5-UART_CK-Pad29)") (class "Default")
      (node (ref "U5") (pin "29") (pinfunction "UART_CK_29") (pintype "passive"))
    )
    (net (code "60") (name "unconnected-(U5-UART_RX-Pad31)") (class "Default")
      (node (ref "U5") (pin "31") (pinfunction "UART_RX_31") (pintype "passive"))
    )
    (net (code "61") (name "unconnected-(U5-UART_TX-Pad30)") (class "Default")
      (node (ref "U5") (pin "30") (pinfunction "UART_TX_30") (pintype "passive"))
    )
    (net (code "62") (name "unconnected-(U5-VBAT-Pad1)") (class "Default")
      (node (ref "U5") (pin "1") (pinfunction "VBAT_1") (pintype "passive"))
    )
    (net (code "63") (name "unconnected-(U6-NC-Pad7)") (class "Default")
      (node (ref "U6") (pin "7") (pinfunction "NC_7") (pintype "passive"))
    )
    (net (code "64") (name "unconnected-(U6-~{ALERT}-Pad6)") (class "Default")
      (node (ref "U6") (pin "6") (pinfunction "~{ALERT}_6") (pintype "passive"))
    )
    (net (code "65") (name "unconnected-(U7-CLK-Pad20)") (class "Default")
      (node (ref "U7") (pin "20") (pinfunction "CLK_20") (pintype "passive"))
    )
    (net (code "66") (name "unconnected-(U7-CMD-Pad19)") (class "Default")
      (node (ref "U7") (pin "19") (pinfunction "CMD_19") (pintype "passive"))
    )
    (net (code "67") (name "unconnected-(U7-IO0-Pad25)") (class "Default")
      (node (ref "U7") (pin "25") (pinfunction "IO0_25") (pintype "passive"))
    )
    (net (code "68") (name "unconnected-(U7-IO2-Pad24)") (class "Default")
      (node (ref "U7") (pin "24") (pinfunction "IO2_24") (pintype "passive"))
    )
    (net (code "69") (name "unconnected-(U7-IO4-Pad26)") (class "Default")
      (node (ref "U7") (pin "26") (pinfunction "IO4_26") (pintype "passive"))
    )
    (net (code "70") (name "unconnected-(U7-IO5-Pad29)") (class "Default")
      (node (ref "U7") (pin "29") (pinfunction "IO5_29") (pintype "passive"))
    )
    (net (code "71") (name "unconnected-(U7-IO12-Pad14)") (class "Default")
      (node (ref "U7") (pin "14") (pinfunction "IO12_14") (pintype "passive"))
    )
    (net (code "72") (name "unconnected-(U7-IO13-Pad16)") (class "Default")
      (node (ref "U7") (pin "16") (pinfunction "IO13_16") (pintype "passive"))
    )
    (net (code "73") (name "unconnected-(U7-IO14-Pad13)") (class "Default")
      (node (ref "U7") (pin "13") (pinfunction "IO14_13") (pintype "passive"))
    )
    (net (code "74") (name "unconnected-(U7-IO15-Pad23)") (class "Default")
      (node (ref "U7") (pin "23") (pinfunction "IO15_23") (pintype "passive"))
    )
    (net (code "75") (name "unconnected-(U7-IO16-Pad27)") (class "Default")
      (node (ref "U7") (pin "27") (pinfunction "IO16_27") (pintype "passive"))
    )
    (net (code "76") (name "unconnected-(U7-IO17-Pad28)") (class "Default")
      (node (ref "U7") (pin "28") (pinfunction "IO17_28") (pintype "passive"))
    )
    (net (code "77") (name "unconnected-(U7-IO18-Pad30)") (class "Default")
      (node (ref "U7") (pin "30") (pinfunction "IO18_30") (pintype "passive"))
    )
    (net (code "78") (name "unconnected-(U7-IO19-Pad31)") (class "Default")
      (node (ref "U7") (pin "31") (pinfunction "IO19_31") (pintype "passive"))
    )
    (net (code "79") (name "unconnected-(U7-IO21-Pad33)") (class "Default")
      (node (ref "U7") (pin "33") (pinfunction "IO21_33") (pintype "passive"))
    )
    (net (code "80") (name "unconnected-(U7-IO22-Pad36)") (class "Default")
      (node (ref "U7") (pin "36") (pinfunction "IO22_36") (pintype "passive"))
    )
    (net (code "81") (name "unconnected-(U7-IO23-Pad37)") (class "Default")
      (node (ref "U7") (pin "37") (pinfunction "IO23_37") (pintype "passive"))
    )
    (net (code "82") (name "unconnected-(U7-IO25-Pad10)") (class "Default")
      (node (ref "U7") (pin "10") (pinfunction "IO25_10") (pintype "passive"))
    )
    (net (code "83") (name "unconnected-(U7-IO26-Pad11)") (class "Default")
      (node (ref "U7") (pin "11") (pinfunction "IO26_11") (pintype "passive"))
    )
    (net (code "84") (name "unconnected-(U7-IO27-Pad12)") (class "Default")
      (node (ref "U7") (pin "12") (pinfunction "IO27_12") (pintype "passive"))
    )
    (net (code "85") (name "unconnected-(U7-IO32-Pad8)") (class "Default")
      (node (ref "U7") (pin "8") (pinfunction "IO32_8") (pintype "passive"))
    )
    (net (code "86") (name "unconnected-(U7-IO33-Pad9)") (class "Default")
      (node (ref "U7") (pin "9") (pinfunction "IO33_9") (pintype "passive"))
    )
    (net (code "87") (name "unconnected-(U7-IO34-Pad6)") (class "Default")
      (node (ref "U7") (pin "6") (pinfunction "IO34_6") (pintype "passive"))
    )
    (net (code "88") (name "unconnected-(U7-IO35-Pad7)") (class "Default")
      (node (ref "U7") (pin "7") (pinfunction "IO35_7") (pintype "passive"))
    )
    (net (code "89") (name "unconnected-(U7-NC-Pad32)") (class "Default")
      (node (ref "U7") (pin "32") (pinfunction "NC_32") (pintype "passive"))
    )
    (net (code "90") (name "unconnected-(U7-SD0-Pad21)") (class "Default")
      (node (ref "U7") (pin "21") (pinfunction "SD0_21") (pintype "passive"))
    )
    (net (code "91") (name "unconnected-(U7-SD1-Pad22)") (class "Default")
      (node (ref "U7") (pin "22") (pinfunction "SD1_22") (pintype "passive"))
    )
    (net (code "92") (name "unconnected-(U7-SD2-Pad17)") (class "Default")
      (node (ref "U7") (pin "17") (pinfunction "SD2_17") (pintype "passive"))
    )
    (net (code "93") (name "unconnected-(U7-SD3-Pad18)") (class "Default")
      (node (ref "U7") (pin "18") (pinfunction "SD3_18") (pintype "passive"))
    )
    (net (code "94") (name "unconnected-(U7-SENSOR_VN-Pad5)") (class "Default")
      (node (ref "U7") (pin "5") (pinfunction "SENSOR_VN_5") (pintype "passive"))
    )
    (net (code "95") (name "unconnected-(U7-SENSOR_VP-Pad4)") (class "Default")
      (node (ref "U7") (pin "4") (pinfunction "SENSOR_VP_4") (pintype "passive"))
    )
  )
)
